# AEDR-7810-Breakout.net
KiCad netlist of a schematic drawn in EAGLE
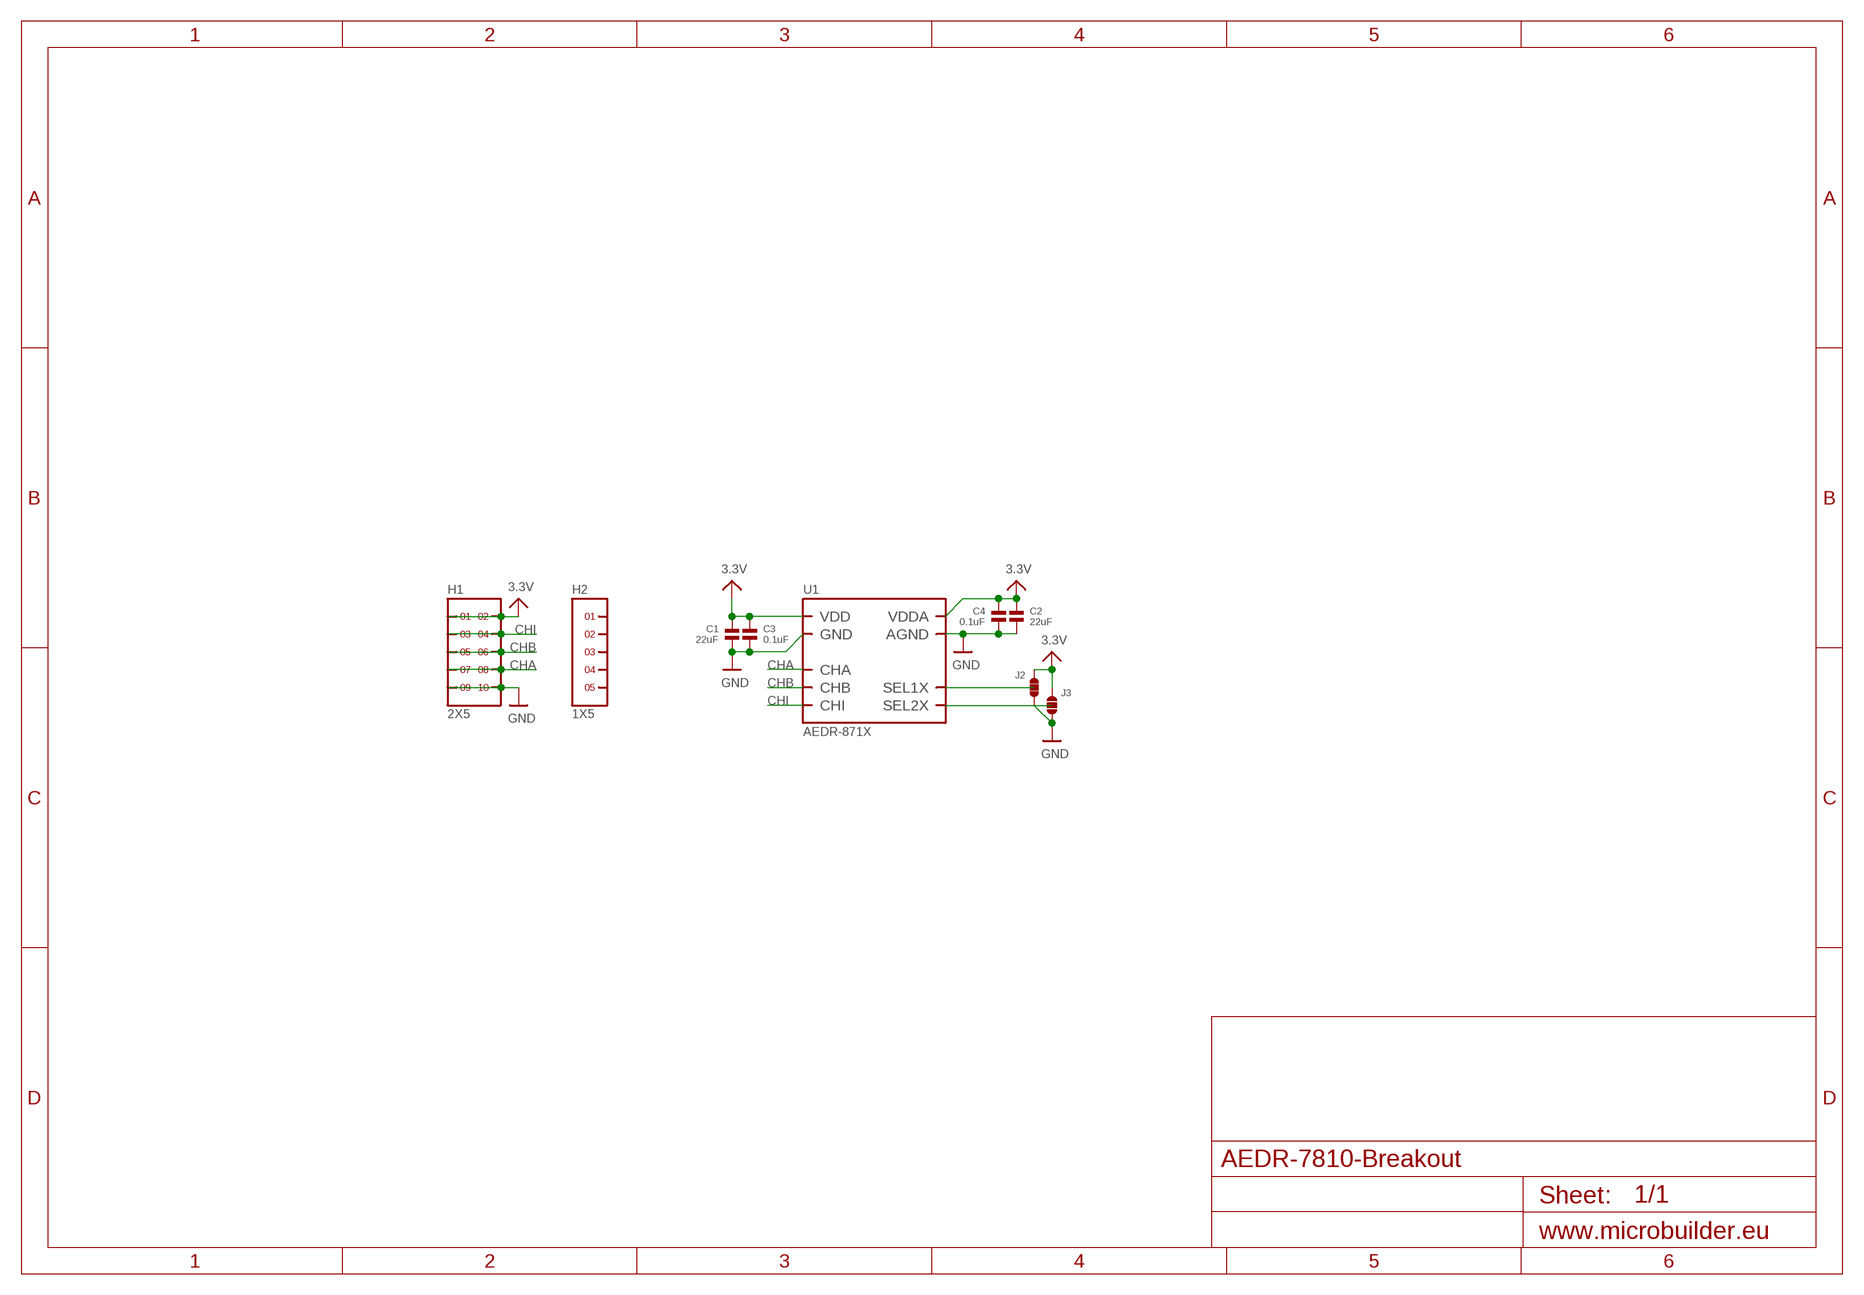
[diagram p0: schematic, sheet 1]

(export (version "E")
  (design (tool "Eeschema 10.0.6"))
  (components
    (comp (ref "C1")
      (value "22uF")
      (footprint "eagle-import:0805")
      (libsource (lib "eagle-import") (part "CAPACITOR.0805"))
    )
    (comp (ref "C2")
      (value "22uF")
      (footprint "eagle-import:0805")
      (libsource (lib "eagle-import") (part "CAPACITOR.0805"))
    )
    (comp (ref "C3")
      (value "0.1uF")
      (footprint "eagle-import:0603")
      (libsource (lib "eagle-import") (part "CAPACITOR.0603"))
    )
    (comp (ref "C4")
      (value "0.1uF")
      (footprint "eagle-import:0603")
      (libsource (lib "eagle-import") (part "CAPACITOR.0603"))
    )
    (comp (ref "H1")
      (value "2X5")
      (footprint "eagle-import:2X5")
      (libsource (lib "eagle-import") (part "2X5"))
    )
    (comp (ref "H2")
      (value "1X5")
      (footprint "eagle-import:1X5")
      (libsource (lib "eagle-import") (part "1X5"))
    )
    (comp (ref "J2")
      (value "SOLDERJUMPER.3.MED.12")
      (footprint "eagle-import:3.MED.12")
      (libsource (lib "eagle-import") (part "SOLDERJUMPER.3.MED.12"))
    )
    (comp (ref "J3")
      (value "SOLDERJUMPER.3.MED.12")
      (footprint "eagle-import:3.MED.12")
      (libsource (lib "eagle-import") (part "SOLDERJUMPER.3.MED.12"))
    )
    (comp (ref "U1")
      (value "AEDR-871X")
      (footprint "eagle-import:AEDR-871X")
      (libsource (lib "eagle-import") (part "AEDR-871X"))
    )
  )
  (nets
    (net (code "1") (name "/CHA") (class "Default")
      (node (ref "H1") (pin "7") (pinfunction "7_7") (pintype "bidirectional"))
      (node (ref "H1") (pin "8") (pinfunction "8_8") (pintype "bidirectional"))
      (node (ref "U1") (pin "7") (pinfunction "CHA_7") (pintype "bidirectional"))
    )
    (net (code "2") (name "/CHB") (class "Default")
      (node (ref "H1") (pin "5") (pinfunction "5_5") (pintype "bidirectional"))
      (node (ref "H1") (pin "6") (pinfunction "6_6") (pintype "bidirectional"))
      (node (ref "U1") (pin "6") (pinfunction "CHB_6") (pintype "bidirectional"))
    )
    (net (code "3") (name "/CHI") (class "Default")
      (node (ref "H1") (pin "3") (pinfunction "3_3") (pintype "bidirectional"))
      (node (ref "H1") (pin "4") (pinfunction "4_4") (pintype "bidirectional"))
      (node (ref "U1") (pin "5") (pinfunction "CHI_5") (pintype "bidirectional"))
    )
    (net (code "4") (name "3.3V") (class "Default")
      (node (ref "C1") (pin "1") (pinfunction "1_1") (pintype "bidirectional"))
      (node (ref "C2") (pin "1") (pinfunction "1_1") (pintype "bidirectional"))
      (node (ref "C3") (pin "1") (pinfunction "1_1") (pintype "bidirectional"))
      (node (ref "C4") (pin "1") (pinfunction "1_1") (pintype "bidirectional"))
      (node (ref "H1") (pin "1") (pinfunction "1_1") (pintype "bidirectional"))
      (node (ref "H1") (pin "2") (pinfunction "2_2") (pintype "bidirectional"))
      (node (ref "J2") (pin "1") (pinfunction "1_1") (pintype "bidirectional"))
      (node (ref "J3") (pin "1") (pinfunction "1_1") (pintype "bidirectional"))
      (node (ref "U1") (pin "1") (pinfunction "VDDA_1") (pintype "bidirectional"))
      (node (ref "U1") (pin "8") (pinfunction "VDD_8") (pintype "bidirectional"))
    )
    (net (code "5") (name "GND") (class "Default")
      (node (ref "C1") (pin "2") (pinfunction "2_2") (pintype "bidirectional"))
      (node (ref "C2") (pin "2") (pinfunction "2_2") (pintype "bidirectional"))
      (node (ref "C3") (pin "2") (pinfunction "2_2") (pintype "bidirectional"))
      (node (ref "C4") (pin "2") (pinfunction "2_2") (pintype "bidirectional"))
      (node (ref "H1") (pin "10") (pinfunction "10_10") (pintype "bidirectional"))
      (node (ref "H1") (pin "9") (pinfunction "9_9") (pintype "bidirectional"))
      (node (ref "J2") (pin "3") (pinfunction "3_3") (pintype "bidirectional"))
      (node (ref "J3") (pin "3") (pinfunction "3_3") (pintype "bidirectional"))
      (node (ref "U1") (pin "2") (pinfunction "AGND_2") (pintype "bidirectional"))
      (node (ref "U1") (pin "PAD") (pinfunction "GND_PAD") (pintype "bidirectional"))
    )
    (net (code "6") (name "Net-(U1-SEL1X)") (class "Default")
      (node (ref "J2") (pin "2") (pinfunction "2_2") (pintype "bidirectional"))
      (node (ref "U1") (pin "3") (pinfunction "SEL1X_3") (pintype "bidirectional"))
    )
    (net (code "7") (name "Net-(U1-SEL2X)") (class "Default")
      (node (ref "J3") (pin "2") (pinfunction "2_2") (pintype "bidirectional"))
      (node (ref "U1") (pin "4") (pinfunction "SEL2X_4") (pintype "bidirectional"))
    )
    (net (code "8") (name "unconnected-(H2-Pad1)") (class "Default")
      (node (ref "H2") (pin "1") (pinfunction "1_1") (pintype "bidirectional"))
    )
    (net (code "9") (name "unconnected-(H2-Pad2)") (class "Default")
      (node (ref "H2") (pin "2") (pinfunction "2_2") (pintype "bidirectional"))
    )
    (net (code "10") (name "unconnected-(H2-Pad3)") (class "Default")
      (node (ref "H2") (pin "3") (pinfunction "3_3") (pintype "bidirectional"))
    )
    (net (code "11") (name "unconnected-(H2-Pad4)") (class "Default")
      (node (ref "H2") (pin "4") (pinfunction "4_4") (pintype "bidirectional"))
    )
    (net (code "12") (name "unconnected-(H2-Pad5)") (class "Default")
      (node (ref "H2") (pin "5") (pinfunction "5_5") (pintype "bidirectional"))
    )
  )
)
